# 01_-_Main.net
KiCad netlist of a schematic drawn in Altium Designer
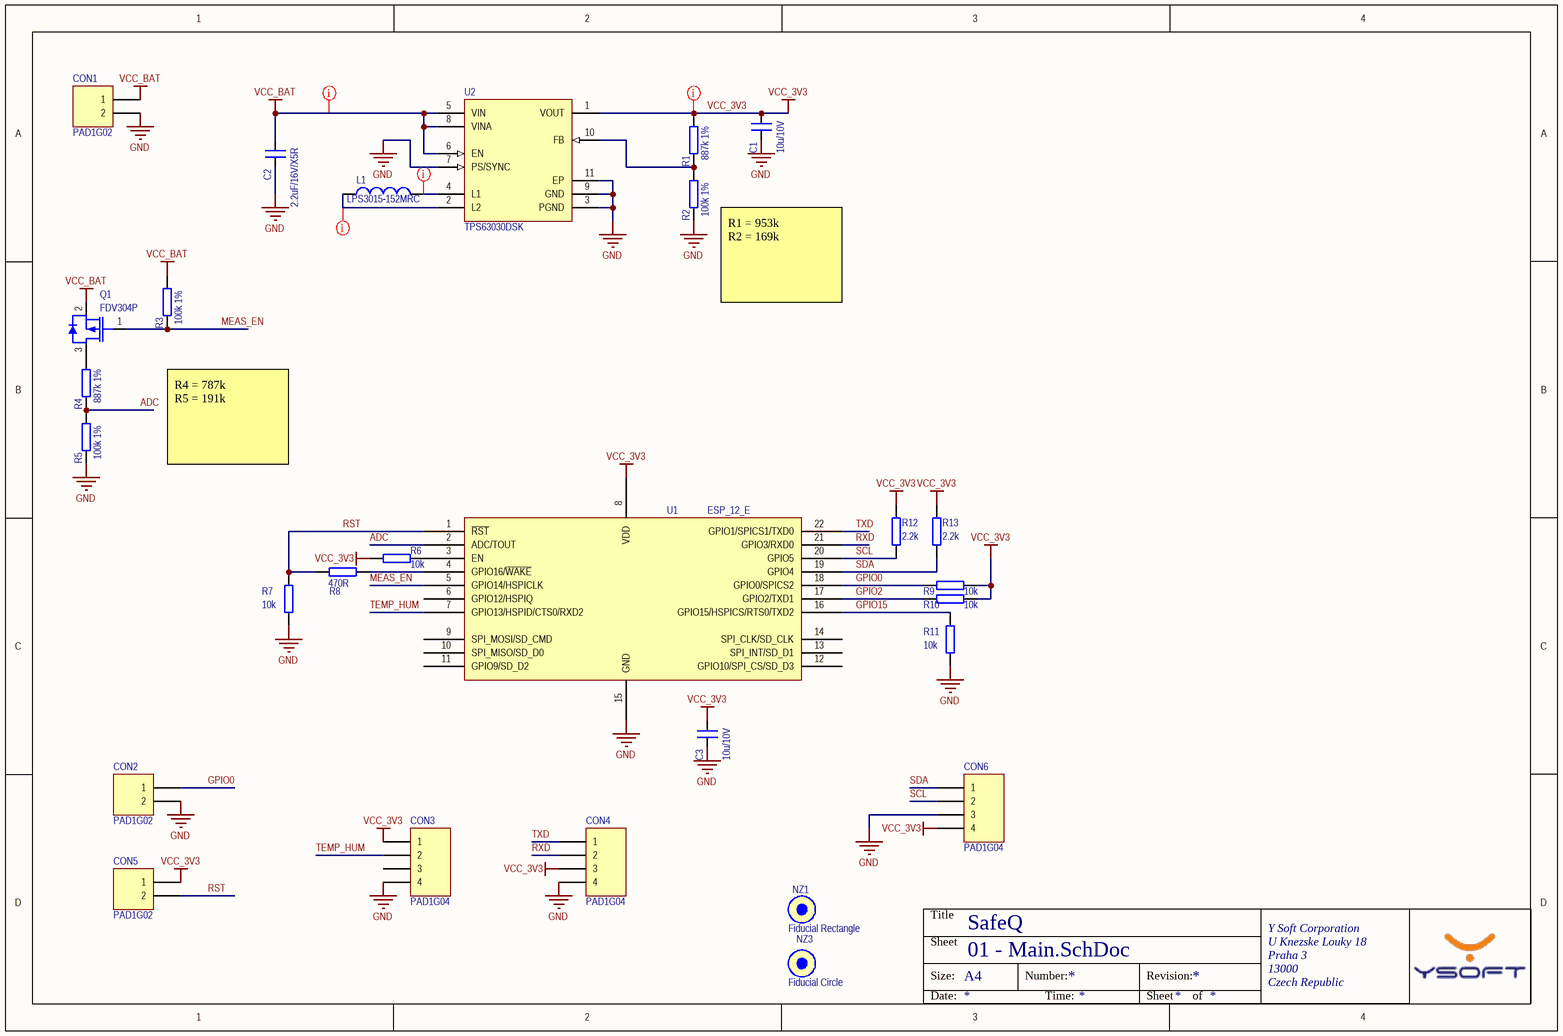
[diagram p0: 01 - Main.SchDoc]

(export (version "E")
  (design (tool "Eeschema 10.0.6"))
  (components
    (comp (ref "C1")
      (value "10u/10V")
      (footprint "C-0805")
      (description "SMD Ceramic Capacitor 0805 10u/10V")
      (libsource (lib "Personal Vault") (part "CapacitorNP"))
    )
    (comp (ref "C2")
      (value "2.2uF/16V/X5R")
      (footprint "C-0603")
      (description "SMD Ceramic Capacitor 0603 2.2uF/16V/X5R")
      (libsource (lib "Personal Vault") (part "CapacitorNP"))
    )
    (comp (ref "C3")
      (value "10u/10V")
      (footprint "C-0805")
      (description "SMD Ceramic Capacitor 0805 10u/10V")
      (libsource (lib "Personal Vault") (part "CapacitorNP"))
    )
    (comp (ref "CON1")
      (value "PAD1G02")
      (footprint "HDR1X02S")
      (description "1x2pin single row pads, 2.54mm")
      (fields (field (name "PUBLISHER") "Altium Limited"))
      (libsource (lib "Personal Vault") (part "Header 2"))
    )
    (comp (ref "CON2")
      (value "PAD1G02")
      (footprint "HDR1X02S")
      (description "1x2pin single row pads, 2.54mm")
      (fields (field (name "PUBLISHER") "Altium Limited"))
      (libsource (lib "Personal Vault") (part "Header 2"))
    )
    (comp (ref "CON3")
      (value "PAD1G04")
      (footprint "HDR1X04S")
      (description "1x4pin single row pads, 2.54mm")
      (libsource (lib "Personal Vault") (part "Header 4"))
    )
    (comp (ref "CON4")
      (value "PAD1G04")
      (footprint "HDR1X04S")
      (description "1x4pin single row pads, 2.54mm")
      (libsource (lib "Personal Vault") (part "Header 4"))
    )
    (comp (ref "CON5")
      (value "PAD1G02")
      (footprint "HDR1X02S")
      (description "1x2pin single row pads, 2.54mm")
      (fields (field (name "PUBLISHER") "Altium Limited"))
      (libsource (lib "Personal Vault") (part "Header 2"))
    )
    (comp (ref "CON6")
      (value "PAD1G04")
      (footprint "HDR1X04S")
      (description "1x4pin single row pads, 2.54mm")
      (libsource (lib "Personal Vault") (part "Header 4"))
    )
    (comp (ref "L1")
      (value "LPS3015-152MRC")
      (footprint "LPS3015")
      (description "Shielded inductor 1.5uH/1.3A 3x3mm")
      (libsource (lib "Personal Vault") (part "Inductor"))
    )
    (comp (ref "NZ1")
      (value "Fiducial Rectangle")
      (footprint "Fiducial Rectangle")
      (libsource (lib "Personal Vault") (part "Fiducial Mark"))
    )
    (comp (ref "NZ3")
      (value "Fiducial Circle")
      (footprint "Fiducial Circle")
      (libsource (lib "Personal Vault") (part "Fiducial Mark"))
    )
    (comp (ref "Q1")
      (value "FDV304P")
      (footprint "SOT23-3L")
      (description "P-Channel Digital FET 25V, 460mA")
      (libsource (lib "Personal Vault") (part "P-MOSFET"))
    )
    (comp (ref "R1")
      (value "887k 1%")
      (footprint "R-0603")
      (description "SMD Resistor 0603 887k 1%")
      (libsource (lib "Personal Vault") (part "Resistor"))
    )
    (comp (ref "R2")
      (value "100k 1%")
      (footprint "R-0603")
      (description "SMD Resistor 0603 100k 1%")
      (libsource (lib "Personal Vault") (part "Resistor"))
    )
    (comp (ref "R3")
      (value "100k 1%")
      (footprint "R-0603")
      (description "SMD Resistor 0603 100k 1%")
      (libsource (lib "Personal Vault") (part "Resistor"))
    )
    (comp (ref "R4")
      (value "887k 1%")
      (footprint "R-0603")
      (description "SMD Resistor 0603 887k 1%")
      (libsource (lib "Personal Vault") (part "Resistor"))
    )
    (comp (ref "R5")
      (value "100k 1%")
      (footprint "R-0603")
      (description "SMD Resistor 0603 100k 1%")
      (libsource (lib "Personal Vault") (part "Resistor"))
    )
    (comp (ref "R6")
      (value "10k")
      (footprint "R-0603")
      (description "SMD Resistor 0603 10k")
      (libsource (lib "Personal Vault") (part "Resistor"))
    )
    (comp (ref "R7")
      (value "10k")
      (footprint "R-0603")
      (description "SMD Resistor 0603 10k")
      (libsource (lib "Personal Vault") (part "Resistor"))
    )
    (comp (ref "R8")
      (value "470R")
      (footprint "R-0603")
      (description "SMD Resistor 0603 470R")
      (libsource (lib "Personal Vault") (part "Resistor"))
    )
    (comp (ref "R9")
      (value "10k")
      (footprint "R-0603")
      (description "SMD Resistor 0603 10k")
      (libsource (lib "Personal Vault") (part "Resistor"))
    )
    (comp (ref "R10")
      (value "10k")
      (footprint "R-0603")
      (description "SMD Resistor 0603 10k")
      (libsource (lib "Personal Vault") (part "Resistor"))
    )
    (comp (ref "R11")
      (value "10k")
      (footprint "R-0603")
      (description "SMD Resistor 0603 10k")
      (libsource (lib "Personal Vault") (part "Resistor"))
    )
    (comp (ref "R12")
      (value "2.2k")
      (footprint "R-0603")
      (description "SMD Resistor 0603 2k2")
      (libsource (lib "Personal Vault") (part "Resistor"))
    )
    (comp (ref "R13")
      (value "2.2k")
      (footprint "R-0603")
      (description "SMD Resistor 0603 2k2")
      (libsource (lib "Personal Vault") (part "Resistor"))
    )
    (comp (ref "U1")
      (value "ESP_12_E")
      (footprint "ESP_12_E")
      (description "ESP-12 Wi-Fi Module by AI-Thinker")
      (libsource (lib "ESP-12") (part "ESP_12_E"))
    )
    (comp (ref "U2")
      (value "TPS63030DSK")
      (footprint "DSK10-2000X1200TP_V")
      (description "High Efficient Single Inductor Buck-Boost Converter with 1-A Switches")
      (libsource (lib "Personal Vault") (part "TPS63030"))
    )
  )
  (nets
    (net (code "1") (name "/ADC") (class "Default")
      (node (ref "R4") (pin "1") (pinfunction "1_1") (pintype "passive"))
      (node (ref "R5") (pin "2") (pinfunction "2_2") (pintype "passive"))
      (node (ref "U1") (pin "2") (pinfunction "ADC/TOUT_2") (pintype "passive"))
    )
    (net (code "2") (name "/GPIO0") (class "Default")
      (node (ref "CON2") (pin "1") (pinfunction "1_1") (pintype "passive"))
      (node (ref "R9") (pin "2") (pinfunction "2_2") (pintype "passive"))
      (node (ref "U1") (pin "18") (pinfunction "GPIO0/SPICS2_18") (pintype "passive"))
    )
    (net (code "3") (name "/GPIO2") (class "Default")
      (node (ref "R10") (pin "2") (pinfunction "2_2") (pintype "passive"))
      (node (ref "U1") (pin "17") (pinfunction "GPIO2/TXD1_17") (pintype "passive"))
    )
    (net (code "4") (name "/GPIO15") (class "Default")
      (node (ref "R11") (pin "2") (pinfunction "2_2") (pintype "passive"))
      (node (ref "U1") (pin "16") (pinfunction "GPIO15/HSPICS/RTS0/TXD2_16") (pintype "passive"))
    )
    (net (code "5") (name "/MEAS_EN") (class "Default")
      (node (ref "Q1") (pin "1") (pinfunction "GATE_1") (pintype "passive"))
      (node (ref "R3") (pin "1") (pinfunction "1_1") (pintype "passive"))
      (node (ref "U1") (pin "5") (pinfunction "GPIO14/HSPICLK_5") (pintype "passive"))
    )
    (net (code "6") (name "/RST") (class "Default")
      (node (ref "CON5") (pin "2") (pinfunction "2_2") (pintype "passive"))
      (node (ref "R7") (pin "2") (pinfunction "2_2") (pintype "passive"))
      (node (ref "R8") (pin "1") (pinfunction "1_1") (pintype "passive"))
      (node (ref "U1") (pin "1") (pinfunction "~{RST}_1") (pintype "passive"))
    )
    (net (code "7") (name "/RXD") (class "Default")
      (node (ref "CON4") (pin "2") (pinfunction "2_2") (pintype "passive"))
      (node (ref "U1") (pin "21") (pinfunction "GPIO3/RXD0_21") (pintype "passive"))
    )
    (net (code "8") (name "/SCL") (class "Default")
      (node (ref "CON6") (pin "2") (pinfunction "2_2") (pintype "passive"))
      (node (ref "R12") (pin "1") (pinfunction "1_1") (pintype "passive"))
      (node (ref "U1") (pin "20") (pinfunction "GPIO5_20") (pintype "passive"))
    )
    (net (code "9") (name "/SDA") (class "Default")
      (node (ref "CON6") (pin "1") (pinfunction "1_1") (pintype "passive"))
      (node (ref "R13") (pin "1") (pinfunction "1_1") (pintype "passive"))
      (node (ref "U1") (pin "19") (pinfunction "GPIO4_19") (pintype "passive"))
    )
    (net (code "10") (name "/TEMP_HUM") (class "Default")
      (node (ref "CON3") (pin "2") (pinfunction "2_2") (pintype "passive"))
      (node (ref "U1") (pin "7") (pinfunction "GPIO13/HSPID/CTS0/RXD2_7") (pintype "passive"))
    )
    (net (code "11") (name "/TXD") (class "Default")
      (node (ref "CON4") (pin "1") (pinfunction "1_1") (pintype "passive"))
      (node (ref "U1") (pin "22") (pinfunction "GPIO1/SPICS1/TXD0_22") (pintype "passive"))
    )
    (net (code "12") (name "GND") (class "Default")
      (node (ref "C1") (pin "1") (pinfunction "1_1") (pintype "passive"))
      (node (ref "C2") (pin "1") (pinfunction "1_1") (pintype "passive"))
      (node (ref "C3") (pin "1") (pinfunction "1_1") (pintype "passive"))
      (node (ref "CON1") (pin "2") (pinfunction "2_2") (pintype "passive"))
      (node (ref "CON2") (pin "2") (pinfunction "2_2") (pintype "passive"))
      (node (ref "CON3") (pin "4") (pinfunction "4_4") (pintype "passive"))
      (node (ref "CON4") (pin "4") (pinfunction "4_4") (pintype "passive"))
      (node (ref "CON6") (pin "3") (pinfunction "3_3") (pintype "passive"))
      (node (ref "R11") (pin "1") (pinfunction "1_1") (pintype "passive"))
      (node (ref "R2") (pin "1") (pinfunction "1_1") (pintype "passive"))
      (node (ref "R5") (pin "1") (pinfunction "1_1") (pintype "passive"))
      (node (ref "R7") (pin "1") (pinfunction "1_1") (pintype "passive"))
      (node (ref "U1") (pin "15") (pinfunction "GND_15") (pintype "passive"))
      (node (ref "U2") (pin "11") (pinfunction "EP_11") (pintype "power_in"))
      (node (ref "U2") (pin "3") (pinfunction "PGND_3") (pintype "power_in"))
      (node (ref "U2") (pin "7") (pinfunction "PS/SYNC_7") (pintype "input"))
      (node (ref "U2") (pin "9") (pinfunction "GND_9") (pintype "power_in"))
    )
    (net (code "13") (name "Net-(Q1-DRAIN)") (class "Default")
      (node (ref "Q1") (pin "3") (pinfunction "DRAIN_3") (pintype "passive"))
      (node (ref "R4") (pin "2") (pinfunction "2_2") (pintype "passive"))
    )
    (net (code "14") (name "Net-(U1-EN)") (class "Default")
      (node (ref "R6") (pin "1") (pinfunction "1_1") (pintype "passive"))
      (node (ref "U1") (pin "3") (pinfunction "EN_3") (pintype "passive"))
    )
    (net (code "15") (name "Net-(U1-GPIO16{slash}~{WAKE})") (class "Default")
      (node (ref "R8") (pin "2") (pinfunction "2_2") (pintype "passive"))
      (node (ref "U1") (pin "4") (pinfunction "GPIO16/~{WAKE}_4") (pintype "passive"))
    )
    (net (code "16") (name "Net-(U2-FB)") (class "Default")
      (node (ref "R1") (pin "1") (pinfunction "1_1") (pintype "passive"))
      (node (ref "R2") (pin "2") (pinfunction "2_2") (pintype "passive"))
      (node (ref "U2") (pin "10") (pinfunction "FB_10") (pintype "input"))
    )
    (net (code "17") (name "Net-(U2-L1)") (class "Default")
      (node (ref "L1") (pin "2") (pinfunction "2_2") (pintype "passive"))
      (node (ref "U2") (pin "4") (pinfunction "L1_4") (pintype "passive"))
    )
    (net (code "18") (name "Net-(U2-L2)") (class "Default")
      (node (ref "L1") (pin "1") (pinfunction "1_1") (pintype "passive"))
      (node (ref "U2") (pin "2") (pinfunction "L2_2") (pintype "passive"))
    )
    (net (code "19") (name "VCC_3V3") (class "Default")
      (node (ref "C1") (pin "2") (pinfunction "2_2") (pintype "passive"))
      (node (ref "C3") (pin "2") (pinfunction "2_2") (pintype "passive"))
      (node (ref "CON3") (pin "1") (pinfunction "1_1") (pintype "passive"))
      (node (ref "CON4") (pin "3") (pinfunction "3_3") (pintype "passive"))
      (node (ref "CON5") (pin "1") (pinfunction "1_1") (pintype "passive"))
      (node (ref "CON6") (pin "4") (pinfunction "4_4") (pintype "passive"))
      (node (ref "R1") (pin "2") (pinfunction "2_2") (pintype "passive"))
      (node (ref "R10") (pin "1") (pinfunction "1_1") (pintype "passive"))
      (node (ref "R12") (pin "2") (pinfunction "2_2") (pintype "passive"))
      (node (ref "R13") (pin "2") (pinfunction "2_2") (pintype "passive"))
      (node (ref "R6") (pin "2") (pinfunction "2_2") (pintype "passive"))
      (node (ref "R9") (pin "1") (pinfunction "1_1") (pintype "passive"))
      (node (ref "U1") (pin "8") (pinfunction "VDD_8") (pintype "passive"))
      (node (ref "U2") (pin "1") (pinfunction "VOUT_1") (pintype "power_in"))
    )
    (net (code "20") (name "VCC_BAT") (class "Default")
      (node (ref "C2") (pin "2") (pinfunction "2_2") (pintype "passive"))
      (node (ref "CON1") (pin "1") (pinfunction "1_1") (pintype "passive"))
      (node (ref "Q1") (pin "2") (pinfunction "SOURCE_2") (pintype "passive"))
      (node (ref "R3") (pin "2") (pinfunction "2_2") (pintype "passive"))
      (node (ref "U2") (pin "5") (pinfunction "VIN_5") (pintype "power_in"))
      (node (ref "U2") (pin "6") (pinfunction "EN_6") (pintype "input"))
      (node (ref "U2") (pin "8") (pinfunction "VINA_8") (pintype "power_in"))
    )
    (net (code "21") (name "unconnected-(CON3-Pad3)") (class "Default")
      (node (ref "CON3") (pin "3") (pinfunction "3_3") (pintype "passive"))
    )
    (net (code "22") (name "unconnected-(U1-GPIO9{slash}SD_D2-Pad11)") (class "Default")
      (node (ref "U1") (pin "11") (pinfunction "GPIO9/SD_D2_11") (pintype "passive"))
    )
    (net (code "23") (name "unconnected-(U1-GPIO10{slash}SPI_CS{slash}SD_D3-Pad12)") (class "Default")
      (node (ref "U1") (pin "12") (pinfunction "GPIO10/SPI_CS/SD_D3_12") (pintype "passive"))
    )
    (net (code "24") (name "unconnected-(U1-GPIO12{slash}HSPIQ-Pad6)") (class "Default")
      (node (ref "U1") (pin "6") (pinfunction "GPIO12/HSPIQ_6") (pintype "passive"))
    )
    (net (code "25") (name "unconnected-(U1-SPI_CLK{slash}SD_CLK-Pad14)") (class "Default")
      (node (ref "U1") (pin "14") (pinfunction "SPI_CLK/SD_CLK_14") (pintype "passive"))
    )
    (net (code "26") (name "unconnected-(U1-SPI_INT{slash}SD_D1-Pad13)") (class "Default")
      (node (ref "U1") (pin "13") (pinfunction "SPI_INT/SD_D1_13") (pintype "passive"))
    )
    (net (code "27") (name "unconnected-(U1-SPI_MISO{slash}SD_D0-Pad10)") (class "Default")
      (node (ref "U1") (pin "10") (pinfunction "SPI_MISO/SD_D0_10") (pintype "passive"))
    )
    (net (code "28") (name "unconnected-(U1-SPI_MOSI{slash}SD_CMD-Pad9)") (class "Default")
      (node (ref "U1") (pin "9") (pinfunction "SPI_MOSI/SD_CMD_9") (pintype "passive"))
    )
  )
)
